# zynthia.net
KiCad netlist of a schematic drawn in EAGLE
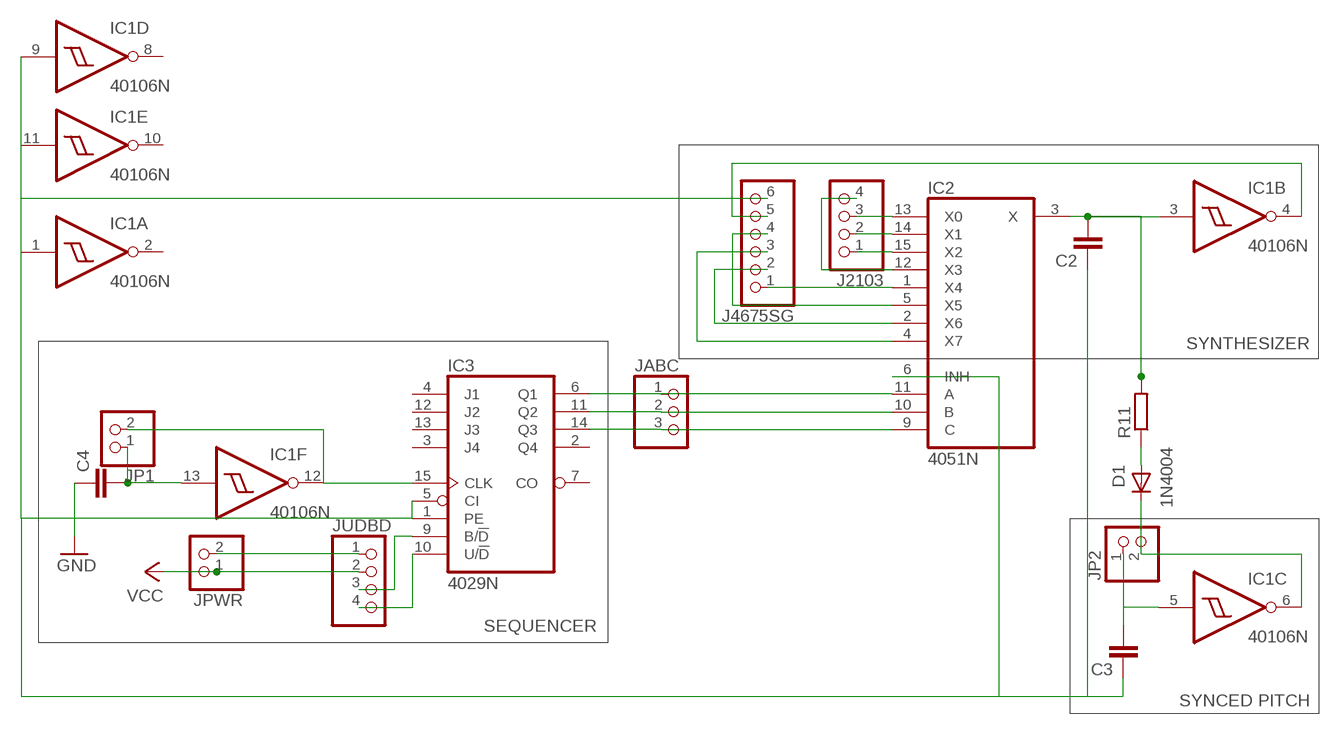
[diagram p0: schematic, sheet 1]

(export (version "E")
  (design (tool "Eeschema 10.0.6"))
  (components
    (comp (ref "C2")
      (value "C-EU025-024X044")
      (footprint "eagle-import:C025-024X044")
      (libsource (lib "eagle-import") (part "C-EU025-024X044"))
    )
    (comp (ref "C3")
      (value "C-EU025-024X044")
      (footprint "eagle-import:C025-024X044")
      (libsource (lib "eagle-import") (part "C-EU025-024X044"))
    )
    (comp (ref "C4")
      (value "C-EU025-024X044")
      (footprint "eagle-import:C025-024X044")
      (libsource (lib "eagle-import") (part "C-EU025-024X044"))
    )
    (comp (ref "D1")
      (value "1N4004")
      (footprint "eagle-import:DO41-10")
      (libsource (lib "eagle-import") (part "1N4004"))
    )
    (comp (ref "IC1")
      (value "40106N")
      (footprint "eagle-import:DIL14")
      (libsource (lib "eagle-import") (part "40106N"))
    )
    (comp (ref "IC2")
      (value "4051N")
      (footprint "eagle-import:DIL16")
      (libsource (lib "eagle-import") (part "4051N"))
    )
    (comp (ref "IC3")
      (value "4029N")
      (footprint "eagle-import:DIL16")
      (libsource (lib "eagle-import") (part "4029N"))
    )
    (comp (ref "J2103")
      (value "PINHD-1X4")
      (footprint "eagle-import:1X04")
      (libsource (lib "eagle-import") (part "PINHD-1X4"))
    )
    (comp (ref "J4675SG")
      (value "PINHD-1X6")
      (footprint "eagle-import:1X06")
      (libsource (lib "eagle-import") (part "PINHD-1X6"))
    )
    (comp (ref "JABC")
      (value "PINHD-1X3")
      (footprint "eagle-import:1X03")
      (libsource (lib "eagle-import") (part "PINHD-1X3"))
    )
    (comp (ref "JP1")
      (value "PINHD-1X2")
      (footprint "eagle-import:1X02")
      (libsource (lib "eagle-import") (part "PINHD-1X2"))
    )
    (comp (ref "JP2")
      (value "PINHD-1X2")
      (footprint "eagle-import:1X02")
      (libsource (lib "eagle-import") (part "PINHD-1X2"))
    )
    (comp (ref "JPWR")
      (value "PINHD-1X2")
      (footprint "eagle-import:1X02")
      (libsource (lib "eagle-import") (part "PINHD-1X2"))
    )
    (comp (ref "JUDBD")
      (value "PINHD-1X4")
      (footprint "eagle-import:1X04")
      (libsource (lib "eagle-import") (part "PINHD-1X4"))
    )
    (comp (ref "R11")
      (value "R-EU_0204/2V")
      (footprint "eagle-import:0204V")
      (libsource (lib "eagle-import") (part "R-EU_0204/2V"))
    )
  )
  (nets
    (net (code "1") (name "GND") (class "Default")
      (node (ref "C4") (pin "1") (pinfunction "1_1") (pintype "passive"))
    )
    (net (code "2") (name "Net-(D1-PadA)") (class "Default")
      (node (ref "D1") (pin "A") (pinfunction "A_A") (pintype "passive"))
      (node (ref "R11") (pin "1") (pinfunction "1_1") (pintype "passive"))
    )
    (net (code "3") (name "Net-(IC1A-I)") (class "Default")
      (node (ref "C2") (pin "1") (pinfunction "1_1") (pintype "passive"))
      (node (ref "C3") (pin "1") (pinfunction "1_1") (pintype "passive"))
      (node (ref "IC1") (pin "1") (pinfunction "I_1") (pintype "input"))
      (node (ref "IC1") (pin "11") (pinfunction "I_11") (pintype "input"))
      (node (ref "IC1") (pin "9") (pinfunction "I_9") (pintype "input"))
      (node (ref "IC2") (pin "6") (pinfunction "INH_6") (pintype "input"))
      (node (ref "IC3") (pin "1") (pinfunction "PE_1") (pintype "input"))
      (node (ref "IC3") (pin "5") (pinfunction "CI_5") (pintype "input"))
      (node (ref "J4675SG") (pin "6") (pinfunction "6_6") (pintype "passive"))
    )
    (net (code "4") (name "Net-(IC1B-I)") (class "Default")
      (node (ref "C2") (pin "2") (pinfunction "2_2") (pintype "passive"))
      (node (ref "IC1") (pin "3") (pinfunction "I_3") (pintype "input"))
      (node (ref "IC2") (pin "3") (pinfunction "X_3") (pintype "bidirectional"))
      (node (ref "R11") (pin "2") (pinfunction "2_2") (pintype "passive"))
    )
    (net (code "5") (name "Net-(IC1B-O)") (class "Default")
      (node (ref "IC1") (pin "4") (pinfunction "O_4") (pintype "output"))
      (node (ref "J4675SG") (pin "5") (pinfunction "5_5") (pintype "passive"))
    )
    (net (code "6") (name "Net-(IC1C-I)") (class "Default")
      (node (ref "C3") (pin "2") (pinfunction "2_2") (pintype "passive"))
      (node (ref "IC1") (pin "5") (pinfunction "I_5") (pintype "input"))
      (node (ref "JP2") (pin "1") (pinfunction "1_1") (pintype "passive"))
    )
    (net (code "7") (name "Net-(IC1C-O)") (class "Default")
      (node (ref "D1") (pin "C") (pinfunction "C_C") (pintype "passive"))
      (node (ref "IC1") (pin "6") (pinfunction "O_6") (pintype "output"))
      (node (ref "JP2") (pin "2") (pinfunction "2_2") (pintype "passive"))
    )
    (net (code "8") (name "Net-(IC1F-I)") (class "Default")
      (node (ref "C4") (pin "2") (pinfunction "2_2") (pintype "passive"))
      (node (ref "IC1") (pin "13") (pinfunction "I_13") (pintype "input"))
      (node (ref "JP1") (pin "1") (pinfunction "1_1") (pintype "passive"))
    )
    (net (code "9") (name "Net-(IC1F-O)") (class "Default")
      (node (ref "IC1") (pin "12") (pinfunction "O_12") (pintype "output"))
      (node (ref "IC3") (pin "15") (pinfunction "CLK_15") (pintype "input"))
      (node (ref "JP1") (pin "2") (pinfunction "2_2") (pintype "passive"))
    )
    (net (code "10") (name "Net-(IC2A-A)") (class "Default")
      (node (ref "IC2") (pin "11") (pinfunction "A_11") (pintype "input"))
      (node (ref "IC3") (pin "6") (pinfunction "Q1_6") (pintype "output"))
      (node (ref "JABC") (pin "1") (pinfunction "1_1") (pintype "passive"))
    )
    (net (code "11") (name "Net-(IC2A-B)") (class "Default")
      (node (ref "IC2") (pin "10") (pinfunction "B_10") (pintype "input"))
      (node (ref "IC3") (pin "11") (pinfunction "Q2_11") (pintype "output"))
      (node (ref "JABC") (pin "2") (pinfunction "2_2") (pintype "passive"))
    )
    (net (code "12") (name "Net-(IC2A-C)") (class "Default")
      (node (ref "IC2") (pin "9") (pinfunction "C_9") (pintype "input"))
      (node (ref "IC3") (pin "14") (pinfunction "Q3_14") (pintype "output"))
      (node (ref "JABC") (pin "3") (pinfunction "3_3") (pintype "passive"))
    )
    (net (code "13") (name "Net-(IC2A-X0)") (class "Default")
      (node (ref "IC2") (pin "13") (pinfunction "X0_13") (pintype "bidirectional"))
      (node (ref "J2103") (pin "3") (pinfunction "3_3") (pintype "passive"))
    )
    (net (code "14") (name "Net-(IC2A-X1)") (class "Default")
      (node (ref "IC2") (pin "14") (pinfunction "X1_14") (pintype "bidirectional"))
      (node (ref "J2103") (pin "2") (pinfunction "2_2") (pintype "passive"))
    )
    (net (code "15") (name "Net-(IC2A-X2)") (class "Default")
      (node (ref "IC2") (pin "15") (pinfunction "X2_15") (pintype "bidirectional"))
      (node (ref "J2103") (pin "1") (pinfunction "1_1") (pintype "passive"))
    )
    (net (code "16") (name "Net-(IC2A-X3)") (class "Default")
      (node (ref "IC2") (pin "12") (pinfunction "X3_12") (pintype "bidirectional"))
      (node (ref "J2103") (pin "4") (pinfunction "4_4") (pintype "passive"))
    )
    (net (code "17") (name "Net-(IC2A-X4)") (class "Default")
      (node (ref "IC2") (pin "1") (pinfunction "X4_1") (pintype "bidirectional"))
      (node (ref "J4675SG") (pin "1") (pinfunction "1_1") (pintype "passive"))
    )
    (net (code "18") (name "Net-(IC2A-X5)") (class "Default")
      (node (ref "IC2") (pin "5") (pinfunction "X5_5") (pintype "bidirectional"))
      (node (ref "J4675SG") (pin "4") (pinfunction "4_4") (pintype "passive"))
    )
    (net (code "19") (name "Net-(IC2A-X6)") (class "Default")
      (node (ref "IC2") (pin "2") (pinfunction "X6_2") (pintype "bidirectional"))
      (node (ref "J4675SG") (pin "2") (pinfunction "2_2") (pintype "passive"))
    )
    (net (code "20") (name "Net-(IC2A-X7)") (class "Default")
      (node (ref "IC2") (pin "4") (pinfunction "X7_4") (pintype "bidirectional"))
      (node (ref "J4675SG") (pin "3") (pinfunction "3_3") (pintype "passive"))
    )
    (net (code "21") (name "Net-(IC3A-B{slash}~{D})") (class "Default")
      (node (ref "IC3") (pin "9") (pinfunction "B/~{D}_9") (pintype "input"))
      (node (ref "JUDBD") (pin "3") (pinfunction "3_3") (pintype "passive"))
    )
    (net (code "22") (name "Net-(IC3A-U{slash}~{D})") (class "Default")
      (node (ref "IC3") (pin "10") (pinfunction "U/~{D}_10") (pintype "input"))
      (node (ref "JUDBD") (pin "4") (pinfunction "4_4") (pintype "passive"))
    )
    (net (code "23") (name "Net-(JPWR-Pad2)") (class "Default")
      (node (ref "JPWR") (pin "2") (pinfunction "2_2") (pintype "passive"))
      (node (ref "JUDBD") (pin "1") (pinfunction "1_1") (pintype "passive"))
    )
    (net (code "24") (name "VCC") (class "Default")
      (node (ref "JPWR") (pin "1") (pinfunction "1_1") (pintype "passive"))
      (node (ref "JUDBD") (pin "2") (pinfunction "2_2") (pintype "passive"))
    )
    (net (code "25") (name "unconnected-(IC1A-O-Pad2)") (class "Default")
      (node (ref "IC1") (pin "2") (pinfunction "O_2") (pintype "output"))
    )
    (net (code "26") (name "unconnected-(IC1D-O-Pad8)") (class "Default")
      (node (ref "IC1") (pin "8") (pinfunction "O_8") (pintype "output"))
    )
    (net (code "27") (name "unconnected-(IC1E-O-Pad10)") (class "Default")
      (node (ref "IC1") (pin "10") (pinfunction "O_10") (pintype "output"))
    )
    (net (code "28") (name "unconnected-(IC3A-CO-Pad7)") (class "Default")
      (node (ref "IC3") (pin "7") (pinfunction "CO_7") (pintype "output"))
    )
    (net (code "29") (name "unconnected-(IC3A-J1-Pad4)") (class "Default")
      (node (ref "IC3") (pin "4") (pinfunction "J1_4") (pintype "input"))
    )
    (net (code "30") (name "unconnected-(IC3A-J2-Pad12)") (class "Default")
      (node (ref "IC3") (pin "12") (pinfunction "J2_12") (pintype "input"))
    )
    (net (code "31") (name "unconnected-(IC3A-J3-Pad13)") (class "Default")
      (node (ref "IC3") (pin "13") (pinfunction "J3_13") (pintype "input"))
    )
    (net (code "32") (name "unconnected-(IC3A-J4-Pad3)") (class "Default")
      (node (ref "IC3") (pin "3") (pinfunction "J4_3") (pintype "input"))
    )
    (net (code "33") (name "unconnected-(IC3A-Q4-Pad2)") (class "Default")
      (node (ref "IC3") (pin "2") (pinfunction "Q4_2") (pintype "output"))
    )
  )
)
